# ESP_LoRa_V1_0.net
KiCad netlist of a schematic drawn in EAGLE
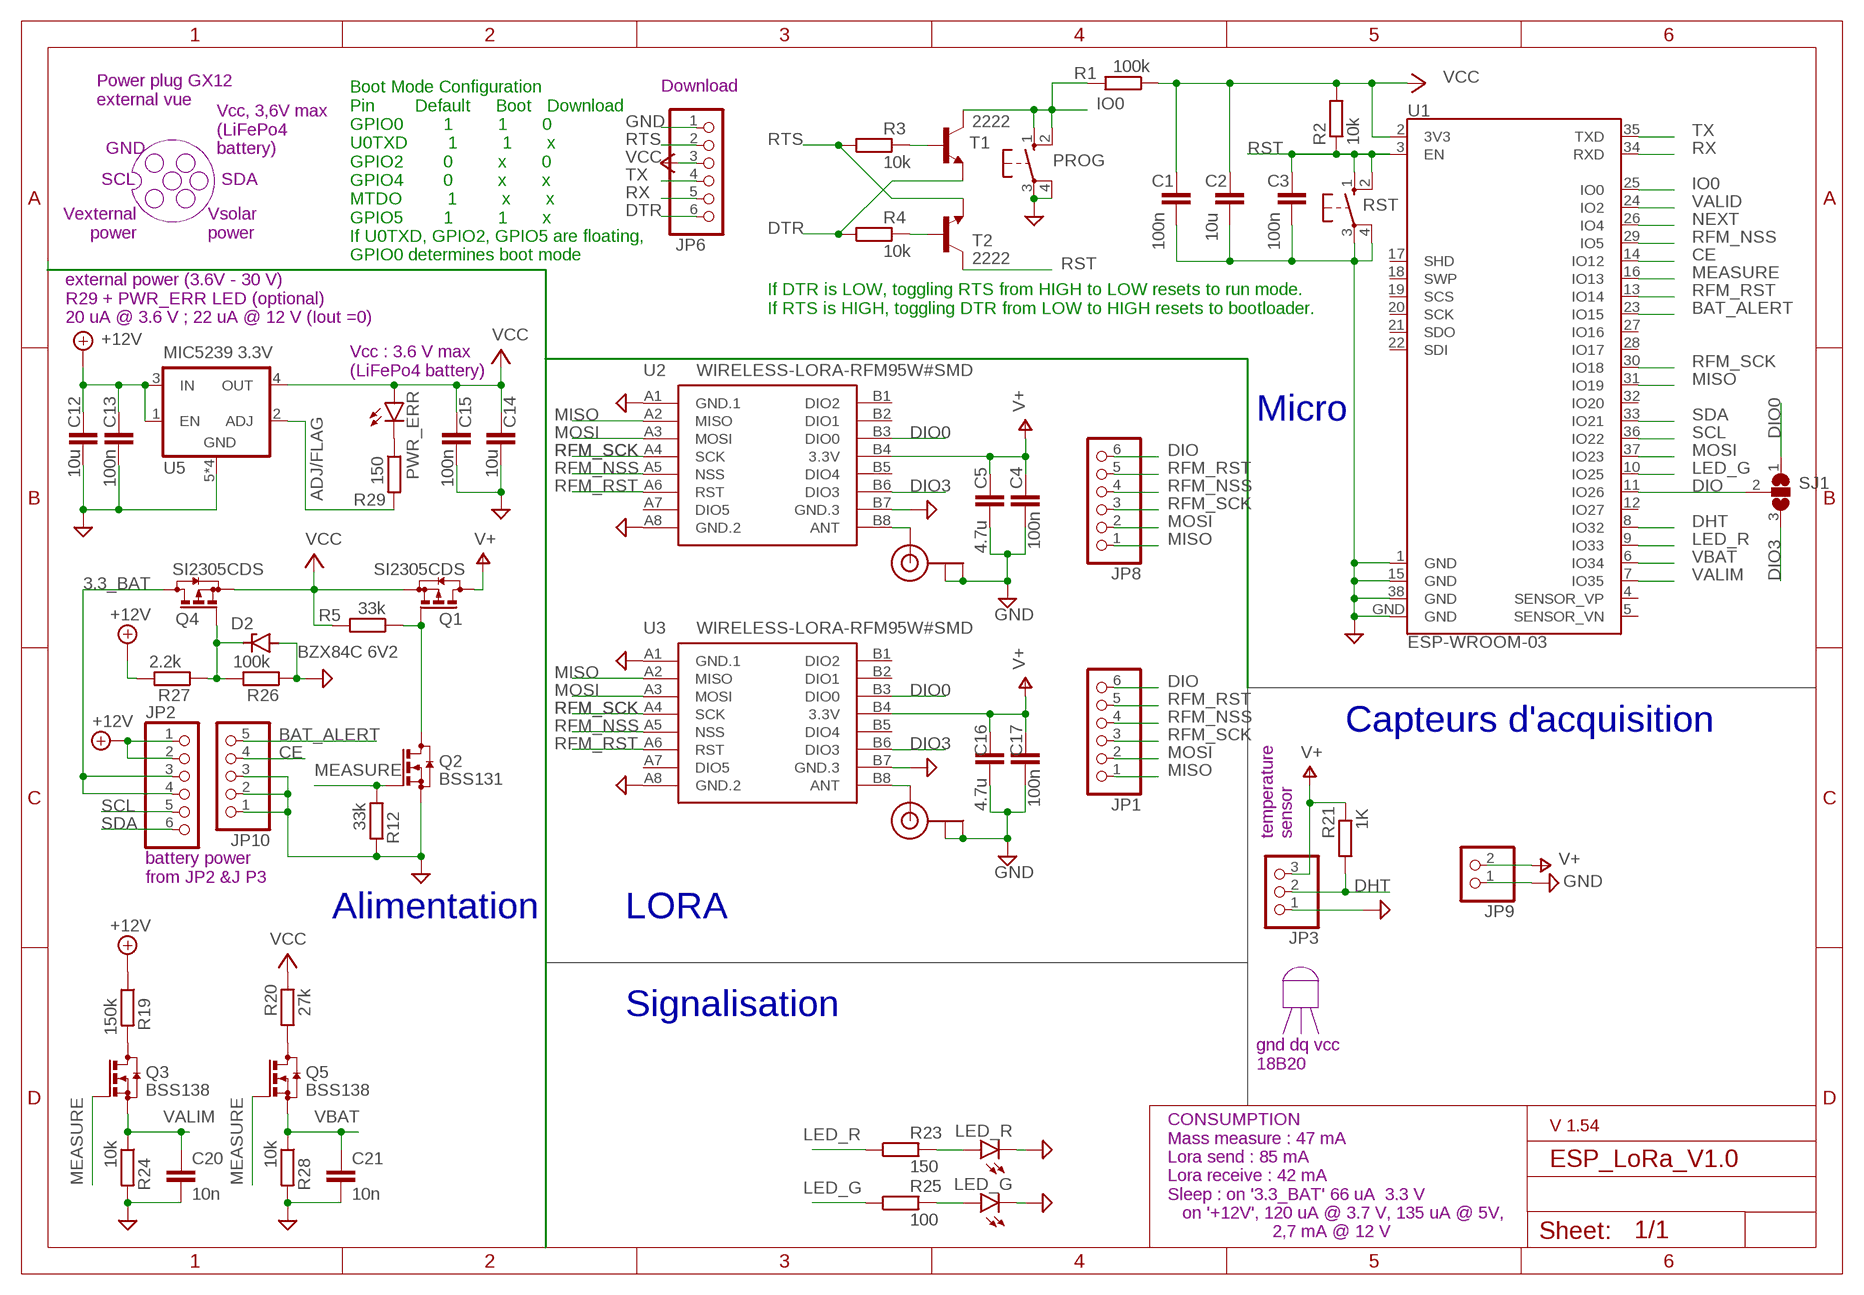
[diagram p0: schematic, sheet 1]

(export (version "E")
  (design (tool "Eeschema 10.0.6"))
  (components
    (comp (ref "C1")
      (value "100n")
      (footprint "eagle-import:C1206")
      (libsource (lib "eagle-import") (part "CC1206"))
    )
    (comp (ref "C2")
      (value "10u")
      (footprint "eagle-import:C1210")
      (libsource (lib "eagle-import") (part "CC1210"))
    )
    (comp (ref "C3")
      (value "100n")
      (footprint "eagle-import:C1206")
      (libsource (lib "eagle-import") (part "CC1206"))
    )
    (comp (ref "C4")
      (value "100n")
      (footprint "eagle-import:C1206")
      (libsource (lib "eagle-import") (part "CC1206"))
    )
    (comp (ref "C5")
      (value "4.7u")
      (footprint "eagle-import:C1210")
      (libsource (lib "eagle-import") (part "CC1210"))
    )
    (comp (ref "C12")
      (value "10u")
      (footprint "eagle-import:C1210")
      (libsource (lib "eagle-import") (part "CC1210"))
    )
    (comp (ref "C13")
      (value "100n")
      (footprint "eagle-import:C1206")
      (libsource (lib "eagle-import") (part "CC1206"))
    )
    (comp (ref "C14")
      (value "10u")
      (footprint "eagle-import:C1210")
      (libsource (lib "eagle-import") (part "CC1210"))
    )
    (comp (ref "C15")
      (value "100n")
      (footprint "eagle-import:C1206")
      (libsource (lib "eagle-import") (part "CC1206"))
    )
    (comp (ref "C16")
      (value "4.7u")
      (footprint "eagle-import:C1210")
      (libsource (lib "eagle-import") (part "CC1210"))
    )
    (comp (ref "C17")
      (value "100n")
      (footprint "eagle-import:C1206")
      (libsource (lib "eagle-import") (part "CC1206"))
    )
    (comp (ref "C20")
      (value "10n")
      (footprint "eagle-import:C1206")
      (libsource (lib "eagle-import") (part "CC1206"))
    )
    (comp (ref "C21")
      (value "10n")
      (footprint "eagle-import:C1206")
      (libsource (lib "eagle-import") (part "CC1206"))
    )
    (comp (ref "D2")
      (value "BZX84C 6V2")
      (footprint "eagle-import:TO236")
      (libsource (lib "eagle-import") (part "BZX84CSMD"))
    )
    (comp (ref "J1")
      (value "U.FL")
      (footprint "eagle-import:U.FL")
      (libsource (lib "eagle-import") (part "U.FL"))
    )
    (comp (ref "J2")
      (value "U.FL")
      (footprint "eagle-import:U.FL")
      (libsource (lib "eagle-import") (part "U.FL"))
    )
    (comp (ref "JP1")
      (value "PINHD-1X6")
      (footprint "eagle-import:1X06")
      (libsource (lib "eagle-import") (part "PINHD-1X6"))
    )
    (comp (ref "JP2")
      (value "PINHD-1X6")
      (footprint "eagle-import:1X06")
      (libsource (lib "eagle-import") (part "PINHD-1X6"))
    )
    (comp (ref "JP3")
      (value "PINHD-1X3")
      (footprint "eagle-import:1X03")
      (libsource (lib "eagle-import") (part "PINHD-1X3"))
    )
    (comp (ref "JP6")
      (value "PINHD-1X6")
      (footprint "eagle-import:1X06")
      (libsource (lib "eagle-import") (part "PINHD-1X6"))
    )
    (comp (ref "JP8")
      (value "PINHD-1X6")
      (footprint "eagle-import:1X06")
      (libsource (lib "eagle-import") (part "PINHD-1X6"))
    )
    (comp (ref "JP9")
      (value "PINHD-1X2")
      (footprint "eagle-import:1X02")
      (libsource (lib "eagle-import") (part "PINHD-1X2"))
    )
    (comp (ref "JP10")
      (value "PINHD-1X5")
      (footprint "eagle-import:1X05")
      (libsource (lib "eagle-import") (part "PINHD-1X5"))
    )
    (comp (ref "LED_G")
      (value "LEDSMT1206")
      (footprint "eagle-import:1206")
      (libsource (lib "eagle-import") (part "LEDSMT1206"))
    )
    (comp (ref "LED_R")
      (value "LEDSMT1206")
      (footprint "eagle-import:1206")
      (libsource (lib "eagle-import") (part "LEDSMT1206"))
    )
    (comp (ref "PROG")
      (value "10-XX")
      (footprint "eagle-import:B3F-10XX")
      (fields (field (name "MPN") "B3F-1000"))
      (libsource (lib "eagle-import") (part "10-XX"))
    )
    (comp (ref "PWR_ERR")
      (value "LEDSMT1206")
      (footprint "eagle-import:1206")
      (libsource (lib "eagle-import") (part "LEDSMT1206"))
    )
    (comp (ref "Q1")
      (value "SI2305CDS")
      (footprint "eagle-import:SOT23")
      (libsource (lib "eagle-import") (part "SI2305CDS"))
    )
    (comp (ref "Q2")
      (value "BSS131")
      (footprint "eagle-import:SOT23")
      (libsource (lib "eagle-import") (part "BSS131"))
    )
    (comp (ref "Q3")
      (value "BSS138")
      (footprint "eagle-import:SOT23")
      (libsource (lib "eagle-import") (part "BSS138"))
    )
    (comp (ref "Q4")
      (value "SI2305CDS")
      (footprint "eagle-import:SOT23")
      (libsource (lib "eagle-import") (part "SI2305CDS"))
    )
    (comp (ref "Q5")
      (value "BSS138")
      (footprint "eagle-import:SOT23")
      (libsource (lib "eagle-import") (part "BSS138"))
    )
    (comp (ref "R1")
      (value "100k")
      (footprint "eagle-import:R1206")
      (libsource (lib "eagle-import") (part "RR1206"))
    )
    (comp (ref "R2")
      (value "10k")
      (footprint "eagle-import:R1206")
      (libsource (lib "eagle-import") (part "RR1206"))
    )
    (comp (ref "R3")
      (value "10k")
      (footprint "eagle-import:R1206")
      (libsource (lib "eagle-import") (part "RR1206"))
    )
    (comp (ref "R4")
      (value "10k")
      (footprint "eagle-import:R1206")
      (libsource (lib "eagle-import") (part "RR1206"))
    )
    (comp (ref "R5")
      (value "33k")
      (footprint "eagle-import:R1206")
      (libsource (lib "eagle-import") (part "RR1206"))
    )
    (comp (ref "R12")
      (value "33k")
      (footprint "eagle-import:R1206")
      (libsource (lib "eagle-import") (part "RR1206"))
    )
    (comp (ref "R19")
      (value "150k")
      (footprint "eagle-import:R1206")
      (libsource (lib "eagle-import") (part "RR1206"))
    )
    (comp (ref "R20")
      (value "27k")
      (footprint "eagle-import:R1206")
      (libsource (lib "eagle-import") (part "RR1206"))
    )
    (comp (ref "R21")
      (value "1K")
      (footprint "eagle-import:R1206")
      (libsource (lib "eagle-import") (part "RR1206"))
    )
    (comp (ref "R23")
      (value "150")
      (footprint "eagle-import:R1206")
      (libsource (lib "eagle-import") (part "RR1206"))
    )
    (comp (ref "R24")
      (value "10k")
      (footprint "eagle-import:R1206")
      (libsource (lib "eagle-import") (part "RR1206"))
    )
    (comp (ref "R25")
      (value "100")
      (footprint "eagle-import:R1206")
      (libsource (lib "eagle-import") (part "RR1206"))
    )
    (comp (ref "R26")
      (value "100k")
      (footprint "eagle-import:R1206")
      (libsource (lib "eagle-import") (part "RR1206"))
    )
    (comp (ref "R27")
      (value "2.2k")
      (footprint "eagle-import:R1206")
      (libsource (lib "eagle-import") (part "RR1206"))
    )
    (comp (ref "R28")
      (value "10k")
      (footprint "eagle-import:R1206")
      (libsource (lib "eagle-import") (part "RR1206"))
    )
    (comp (ref "R29")
      (value "150")
      (footprint "eagle-import:R1206")
      (libsource (lib "eagle-import") (part "RR1206"))
    )
    (comp (ref "RST")
      (value "10-XX")
      (footprint "eagle-import:B3F-10XX")
      (fields (field (name "MPN") "B3F-1000"))
      (libsource (lib "eagle-import") (part "10-XX"))
    )
    (comp (ref "SJ1")
      (value "SJ2W")
      (footprint "eagle-import:SJ_2")
      (libsource (lib "eagle-import") (part "SJ2W"))
    )
    (comp (ref "T1")
      (value "2222")
      (footprint "eagle-import:SOT23-BEC")
      (libsource (lib "eagle-import") (part "-NPN-SOT23-BECMMBT2222ALT1"))
    )
    (comp (ref "T2")
      (value "2222")
      (footprint "eagle-import:SOT23-BEC")
      (libsource (lib "eagle-import") (part "-NPN-SOT23-BECMMBT2222ALT1"))
    )
    (comp (ref "U1")
      (value "ESP-WROOM-03")
      (footprint "eagle-import:ESP-WROOM-03")
      (libsource (lib "eagle-import") (part "ESP-WROOM-03"))
    )
    (comp (ref "U2")
      (value "WIRELESS-LORA-RFM95W#SMD")
      (footprint "eagle-import:WIRELESS-LORA-RFM95W#SMD")
      (libsource (lib "eagle-import") (part "WIRELESS-LORA-RFM95W#SMD"))
    )
    (comp (ref "U3")
      (value "WIRELESS-LORA-RFM95W#SMD")
      (footprint "eagle-import:WIRELESS-LORA-RFM95W#SMD")
      (libsource (lib "eagle-import") (part "WIRELESS-LORA-RFM95W#SMD"))
    )
    (comp (ref "U5")
      (value "MIC5239 3.3V")
      (footprint "eagle-import:MSOP08")
      (libsource (lib "eagle-import") (part "MIC5239-ADJMM"))
    )
  )
  (nets
    (net (code "1") (name "+12V") (class "Default")
      (node (ref "C12") (pin "1") (pinfunction "1_1") (pintype "passive"))
      (node (ref "C13") (pin "1") (pinfunction "1_1") (pintype "passive"))
      (node (ref "JP2") (pin "1") (pinfunction "1_1") (pintype "passive"))
      (node (ref "JP2") (pin "2") (pinfunction "2_2") (pintype "passive"))
      (node (ref "R19") (pin "1") (pinfunction "1_1") (pintype "passive"))
      (node (ref "R27") (pin "2") (pinfunction "2_2") (pintype "passive"))
      (node (ref "U5") (pin "1") (pinfunction "EN_1") (pintype "input"))
      (node (ref "U5") (pin "3") (pinfunction "IN_3") (pintype "input"))
    )
    (net (code "2") (name "/3.3_BAT") (class "Default")
      (node (ref "JP2") (pin "3") (pinfunction "3_3") (pintype "passive"))
      (node (ref "JP2") (pin "4") (pinfunction "4_4") (pintype "passive"))
      (node (ref "Q4") (pin "3") (pinfunction "D_3") (pintype "passive"))
    )
    (net (code "3") (name "/ADJ{slash}FLAG") (class "Default")
      (node (ref "R29") (pin "2") (pinfunction "2_2") (pintype "passive"))
      (node (ref "U5") (pin "2") (pinfunction "ADJ_2") (pintype "passive"))
    )
    (net (code "4") (name "/BAT_ALERT") (class "Default")
      (node (ref "JP10") (pin "5") (pinfunction "5_5") (pintype "passive"))
      (node (ref "U1") (pin "23") (pinfunction "IO15_23") (pintype "bidirectional"))
    )
    (net (code "5") (name "/CE") (class "Default")
      (node (ref "JP10") (pin "4") (pinfunction "4_4") (pintype "passive"))
      (node (ref "U1") (pin "14") (pinfunction "IO12_14") (pintype "bidirectional"))
    )
    (net (code "6") (name "/DHT") (class "Default")
      (node (ref "JP3") (pin "2") (pinfunction "2_2") (pintype "passive"))
      (node (ref "R21") (pin "1") (pinfunction "1_1") (pintype "passive"))
      (node (ref "U1") (pin "8") (pinfunction "IO32_8") (pintype "bidirectional"))
    )
    (net (code "7") (name "/DIO") (class "Default")
      (node (ref "JP1") (pin "6") (pinfunction "6_6") (pintype "passive"))
      (node (ref "JP8") (pin "6") (pinfunction "6_6") (pintype "passive"))
      (node (ref "SJ1") (pin "2") (pinfunction "2_2") (pintype "passive"))
      (node (ref "U1") (pin "11") (pinfunction "IO26_11") (pintype "bidirectional"))
    )
    (net (code "8") (name "/DIO0") (class "Default")
      (node (ref "SJ1") (pin "1") (pinfunction "1_1") (pintype "passive"))
      (node (ref "U2") (pin "B3") (pinfunction "DIO0_B3") (pintype "bidirectional"))
      (node (ref "U3") (pin "B3") (pinfunction "DIO0_B3") (pintype "bidirectional"))
    )
    (net (code "9") (name "/DIO3") (class "Default")
      (node (ref "SJ1") (pin "3") (pinfunction "3_3") (pintype "passive"))
      (node (ref "U2") (pin "B6") (pinfunction "DIO3_B6") (pintype "bidirectional"))
      (node (ref "U3") (pin "B6") (pinfunction "DIO3_B6") (pintype "bidirectional"))
    )
    (net (code "10") (name "/DTR") (class "Default")
      (node (ref "JP6") (pin "6") (pinfunction "6_6") (pintype "passive"))
      (node (ref "R4") (pin "1") (pinfunction "1_1") (pintype "passive"))
      (node (ref "T1") (pin "E") (pinfunction "E_E") (pintype "passive"))
    )
    (net (code "11") (name "/IO0") (class "Default")
      (node (ref "PROG") (pin "1") (pinfunction "S_1") (pintype "passive"))
      (node (ref "PROG") (pin "2") (pinfunction "S1_2") (pintype "passive"))
      (node (ref "R1") (pin "2") (pinfunction "2_2") (pintype "passive"))
      (node (ref "T1") (pin "C") (pinfunction "C_C") (pintype "passive"))
      (node (ref "U1") (pin "25") (pinfunction "IO0_25") (pintype "bidirectional"))
    )
    (net (code "12") (name "/LED_G") (class "Default")
      (node (ref "R25") (pin "1") (pinfunction "1_1") (pintype "passive"))
      (node (ref "U1") (pin "10") (pinfunction "IO25_10") (pintype "bidirectional"))
    )
    (net (code "13") (name "/LED_R") (class "Default")
      (node (ref "R23") (pin "1") (pinfunction "1_1") (pintype "passive"))
      (node (ref "U1") (pin "9") (pinfunction "IO33_9") (pintype "bidirectional"))
    )
    (net (code "14") (name "/MEASURE") (class "Default")
      (node (ref "Q2") (pin "1") (pinfunction "G_1") (pintype "passive"))
      (node (ref "Q3") (pin "1") (pinfunction "G_1") (pintype "passive"))
      (node (ref "Q5") (pin "1") (pinfunction "G_1") (pintype "passive"))
      (node (ref "R12") (pin "1") (pinfunction "1_1") (pintype "passive"))
      (node (ref "U1") (pin "16") (pinfunction "IO13_16") (pintype "bidirectional"))
    )
    (net (code "15") (name "/MISO") (class "Default")
      (node (ref "JP1") (pin "1") (pinfunction "1_1") (pintype "passive"))
      (node (ref "JP8") (pin "1") (pinfunction "1_1") (pintype "passive"))
      (node (ref "U1") (pin "31") (pinfunction "IO19_31") (pintype "bidirectional"))
      (node (ref "U2") (pin "A2") (pinfunction "MISO_A2") (pintype "bidirectional"))
      (node (ref "U3") (pin "A2") (pinfunction "MISO_A2") (pintype "bidirectional"))
    )
    (net (code "16") (name "/MOSI") (class "Default")
      (node (ref "JP1") (pin "2") (pinfunction "2_2") (pintype "passive"))
      (node (ref "JP8") (pin "2") (pinfunction "2_2") (pintype "passive"))
      (node (ref "U1") (pin "37") (pinfunction "IO23_37") (pintype "bidirectional"))
      (node (ref "U2") (pin "A3") (pinfunction "MOSI_A3") (pintype "bidirectional"))
      (node (ref "U3") (pin "A3") (pinfunction "MOSI_A3") (pintype "bidirectional"))
    )
    (net (code "17") (name "/NEXT") (class "Default")
      (node (ref "U1") (pin "26") (pinfunction "IO4_26") (pintype "bidirectional"))
    )
    (net (code "18") (name "/RFM_NSS") (class "Default")
      (node (ref "JP1") (pin "4") (pinfunction "4_4") (pintype "passive"))
      (node (ref "JP8") (pin "4") (pinfunction "4_4") (pintype "passive"))
      (node (ref "U1") (pin "29") (pinfunction "IO5_29") (pintype "bidirectional"))
      (node (ref "U2") (pin "A5") (pinfunction "NSS_A5") (pintype "bidirectional"))
      (node (ref "U3") (pin "A5") (pinfunction "NSS_A5") (pintype "bidirectional"))
    )
    (net (code "19") (name "/RFM_RST") (class "Default")
      (node (ref "JP1") (pin "5") (pinfunction "5_5") (pintype "passive"))
      (node (ref "JP8") (pin "5") (pinfunction "5_5") (pintype "passive"))
      (node (ref "U1") (pin "13") (pinfunction "IO14_13") (pintype "bidirectional"))
      (node (ref "U2") (pin "A6") (pinfunction "RST_A6") (pintype "bidirectional"))
      (node (ref "U3") (pin "A6") (pinfunction "RST_A6") (pintype "bidirectional"))
    )
    (net (code "20") (name "/RFM_SCK") (class "Default")
      (node (ref "JP1") (pin "3") (pinfunction "3_3") (pintype "passive"))
      (node (ref "JP8") (pin "3") (pinfunction "3_3") (pintype "passive"))
      (node (ref "U1") (pin "30") (pinfunction "IO18_30") (pintype "bidirectional"))
      (node (ref "U2") (pin "A4") (pinfunction "SCK_A4") (pintype "bidirectional"))
      (node (ref "U3") (pin "A4") (pinfunction "SCK_A4") (pintype "bidirectional"))
    )
    (net (code "21") (name "/RST") (class "Default")
      (node (ref "C3") (pin "1") (pinfunction "1_1") (pintype "passive"))
      (node (ref "R2") (pin "1") (pinfunction "1_1") (pintype "passive"))
      (node (ref "RST") (pin "1") (pinfunction "S_1") (pintype "passive"))
      (node (ref "RST") (pin "2") (pinfunction "S1_2") (pintype "passive"))
      (node (ref "T2") (pin "C") (pinfunction "C_C") (pintype "passive"))
      (node (ref "U1") (pin "3") (pinfunction "EN_3") (pintype "bidirectional"))
    )
    (net (code "22") (name "/RTS") (class "Default")
      (node (ref "JP6") (pin "2") (pinfunction "2_2") (pintype "passive"))
      (node (ref "R3") (pin "1") (pinfunction "1_1") (pintype "passive"))
      (node (ref "T2") (pin "E") (pinfunction "E_E") (pintype "passive"))
    )
    (net (code "23") (name "/RX") (class "Default")
      (node (ref "JP6") (pin "5") (pinfunction "5_5") (pintype "passive"))
      (node (ref "U1") (pin "34") (pinfunction "RXD_34") (pintype "bidirectional"))
    )
    (net (code "24") (name "/SCL") (class "Default")
      (node (ref "JP2") (pin "5") (pinfunction "5_5") (pintype "passive"))
      (node (ref "U1") (pin "36") (pinfunction "IO22_36") (pintype "bidirectional"))
    )
    (net (code "25") (name "/SDA") (class "Default")
      (node (ref "JP2") (pin "6") (pinfunction "6_6") (pintype "passive"))
      (node (ref "U1") (pin "33") (pinfunction "IO21_33") (pintype "bidirectional"))
    )
    (net (code "26") (name "/TX") (class "Default")
      (node (ref "JP6") (pin "4") (pinfunction "4_4") (pintype "passive"))
      (node (ref "U1") (pin "35") (pinfunction "TXD_35") (pintype "bidirectional"))
    )
    (net (code "27") (name "/VALID") (class "Default")
      (node (ref "U1") (pin "24") (pinfunction "IO2_24") (pintype "bidirectional"))
    )
    (net (code "28") (name "/VALIM") (class "Default")
      (node (ref "C20") (pin "1") (pinfunction "1_1") (pintype "passive"))
      (node (ref "Q3") (pin "2") (pinfunction "S_2") (pintype "passive"))
      (node (ref "R24") (pin "1") (pinfunction "1_1") (pintype "passive"))
      (node (ref "U1") (pin "7") (pinfunction "IO35_7") (pintype "bidirectional"))
    )
    (net (code "29") (name "/VBAT") (class "Default")
      (node (ref "C21") (pin "1") (pinfunction "1_1") (pintype "passive"))
      (node (ref "Q5") (pin "2") (pinfunction "S_2") (pintype "passive"))
      (node (ref "R28") (pin "1") (pinfunction "1_1") (pintype "passive"))
      (node (ref "U1") (pin "6") (pinfunction "IO34_6") (pintype "bidirectional"))
    )
    (net (code "30") (name "GND") (class "Default")
      (node (ref "C1") (pin "2") (pinfunction "2_2") (pintype "passive"))
      (node (ref "C12") (pin "2") (pinfunction "2_2") (pintype "passive"))
      (node (ref "C13") (pin "2") (pinfunction "2_2") (pintype "passive"))
      (node (ref "C14") (pin "2") (pinfunction "2_2") (pintype "passive"))
      (node (ref "C15") (pin "2") (pinfunction "2_2") (pintype "passive"))
      (node (ref "C16") (pin "2") (pinfunction "2_2") (pintype "passive"))
      (node (ref "C17") (pin "2") (pinfunction "2_2") (pintype "passive"))
      (node (ref "C2") (pin "2") (pinfunction "2_2") (pintype "passive"))
      (node (ref "C20") (pin "2") (pinfunction "2_2") (pintype "passive"))
      (node (ref "C21") (pin "2") (pinfunction "2_2") (pintype "passive"))
      (node (ref "C3") (pin "2") (pinfunction "2_2") (pintype "passive"))
      (node (ref "C4") (pin "2") (pinfunction "2_2") (pintype "passive"))
      (node (ref "C5") (pin "2") (pinfunction "2_2") (pintype "passive"))
      (node (ref "D2") (pin "A") (pinfunction "A_A") (pintype "passive"))
      (node (ref "J1") (pin "1") (pinfunction "GND_1") (pintype "passive"))
      (node (ref "J1") (pin "2") (pinfunction "GND_2") (pintype "passive"))
      (node (ref "J2") (pin "1") (pinfunction "GND_1") (pintype "passive"))
      (node (ref "J2") (pin "2") (pinfunction "GND_2") (pintype "passive"))
      (node (ref "JP10") (pin "1") (pinfunction "1_1") (pintype "passive"))
      (node (ref "JP10") (pin "2") (pinfunction "2_2") (pintype "passive"))
      (node (ref "JP10") (pin "3") (pinfunction "3_3") (pintype "passive"))
      (node (ref "JP3") (pin "1") (pinfunction "1_1") (pintype "passive"))
      (node (ref "JP6") (pin "1") (pinfunction "1_1") (pintype "passive"))
      (node (ref "JP9") (pin "1") (pinfunction "1_1") (pintype "passive"))
      (node (ref "LED_G") (pin "C") (pinfunction "C_C") (pintype "passive"))
      (node (ref "LED_R") (pin "C") (pinfunction "C_C") (pintype "passive"))
      (node (ref "PROG") (pin "3") (pinfunction "P_3") (pintype "passive"))
      (node (ref "PROG") (pin "4") (pinfunction "P1_4") (pintype "passive"))
      (node (ref "Q2") (pin "2") (pinfunction "S_2") (pintype "passive"))
      (node (ref "R12") (pin "2") (pinfunction "2_2") (pintype "passive"))
      (node (ref "R24") (pin "2") (pinfunction "2_2") (pintype "passive"))
      (node (ref "R26") (pin "1") (pinfunction "1_1") (pintype "passive"))
      (node (ref "R28") (pin "2") (pinfunction "2_2") (pintype "passive"))
      (node (ref "RST") (pin "3") (pinfunction "P_3") (pintype "passive"))
      (node (ref "RST") (pin "4") (pinfunction "P1_4") (pintype "passive"))
      (node (ref "U1") (pin "1") (pinfunction "GND_1") (pintype "bidirectional"))
      (node (ref "U1") (pin "15") (pinfunction "GND_15") (pintype "bidirectional"))
      (node (ref "U1") (pin "38") (pinfunction "GND_38") (pintype "bidirectional"))
      (node (ref "U1") (pin "GND") (pinfunction "GND_GND") (pintype "bidirectional"))
      (node (ref "U2") (pin "A1") (pinfunction "GND.1_A1") (pintype "power_in"))
      (node (ref "U2") (pin "A8") (pinfunction "GND.2_A8") (pintype "power_in"))
      (node (ref "U2") (pin "B7") (pinfunction "GND.3_B7") (pintype "power_in"))
      (node (ref "U3") (pin "A1") (pinfunction "GND.1_A1") (pintype "power_in"))
      (node (ref "U3") (pin "A8") (pinfunction "GND.2_A8") (pintype "power_in"))
      (node (ref "U3") (pin "B7") (pinfunction "GND.3_B7") (pintype "power_in"))
      (node (ref "U5") (pin "5") (pinfunction "GND_5") (pintype "power_in"))
      (node (ref "U5") (pin "6") (pinfunction "GND_6") (pintype "power_in"))
      (node (ref "U5") (pin "7") (pinfunction "GND_7") (pintype "power_in"))
      (node (ref "U5") (pin "8") (pinfunction "GND_8") (pintype "power_in"))
    )
    (net (code "31") (name "Net-(J1-SIGNAL)") (class "Default")
      (node (ref "J1") (pin "3") (pinfunction "SIGNAL_3") (pintype "passive"))
      (node (ref "U3") (pin "B8") (pinfunction "ANT_B8") (pintype "passive"))
    )
    (net (code "32") (name "Net-(J2-SIGNAL)") (class "Default")
      (node (ref "J2") (pin "3") (pinfunction "SIGNAL_3") (pintype "passive"))
      (node (ref "U2") (pin "B8") (pinfunction "ANT_B8") (pintype "passive"))
    )
    (net (code "33") (name "Net-(LED_G-PadA)") (class "Default")
      (node (ref "LED_G") (pin "A") (pinfunction "A_A") (pintype "passive"))
      (node (ref "R25") (pin "2") (pinfunction "2_2") (pintype "passive"))
    )
    (net (code "34") (name "Net-(LED_R-PadA)") (class "Default")
      (node (ref "LED_R") (pin "A") (pinfunction "A_A") (pintype "passive"))
      (node (ref "R23") (pin "2") (pinfunction "2_2") (pintype "passive"))
    )
    (net (code "35") (name "Net-(PWR_ERR-PadC)") (class "Default")
      (node (ref "PWR_ERR") (pin "C") (pinfunction "C_C") (pintype "passive"))
      (node (ref "R29") (pin "1") (pinfunction "1_1") (pintype "passive"))
    )
    (net (code "36") (name "Net-(Q1-G)") (class "Default")
      (node (ref "Q1") (pin "1") (pinfunction "G_1") (pintype "passive"))
      (node (ref "Q2") (pin "3") (pinfunction "D_3") (pintype "passive"))
      (node (ref "R5") (pin "1") (pinfunction "1_1") (pintype "passive"))
    )
    (net (code "37") (name "Net-(Q3-D)") (class "Default")
      (node (ref "Q3") (pin "3") (pinfunction "D_3") (pintype "passive"))
      (node (ref "R19") (pin "2") (pinfunction "2_2") (pintype "passive"))
    )
    (net (code "38") (name "Net-(Q4-G)") (class "Default")
      (node (ref "D2") (pin "C") (pinfunction "C_C") (pintype "passive"))
      (node (ref "Q4") (pin "1") (pinfunction "G_1") (pintype "passive"))
      (node (ref "R26") (pin "2") (pinfunction "2_2") (pintype "passive"))
      (node (ref "R27") (pin "1") (pinfunction "1_1") (pintype "passive"))
    )
    (net (code "39") (name "Net-(Q5-D)") (class "Default")
      (node (ref "Q5") (pin "3") (pinfunction "D_3") (pintype "passive"))
      (node (ref "R20") (pin "1") (pinfunction "1_1") (pintype "passive"))
    )
    (net (code "40") (name "Net-(R3-Pad2)") (class "Default")
      (node (ref "R3") (pin "2") (pinfunction "2_2") (pintype "passive"))
      (node (ref "T1") (pin "B") (pinfunction "B_B") (pintype "passive"))
    )
    (net (code "41") (name "Net-(R4-Pad2)") (class "Default")
      (node (ref "R4") (pin "2") (pinfunction "2_2") (pintype "passive"))
      (node (ref "T2") (pin "B") (pinfunction "B_B") (pintype "passive"))
    )
    (net (code "42") (name "V+") (class "Default")
      (node (ref "C16") (pin "1") (pinfunction "1_1") (pintype "passive"))
      (node (ref "C17") (pin "1") (pinfunction "1_1") (pintype "passive"))
      (node (ref "C4") (pin "1") (pinfunction "1_1") (pintype "passive"))
      (node (ref "C5") (pin "1") (pinfunction "1_1") (pintype "passive"))
      (node (ref "JP3") (pin "3") (pinfunction "3_3") (pintype "passive"))
      (node (ref "JP9") (pin "2") (pinfunction "2_2") (pintype "passive"))
      (node (ref "Q1") (pin "3") (pinfunction "D_3") (pintype "passive"))
      (node (ref "R21") (pin "2") (pinfunction "2_2") (pintype "passive"))
      (node (ref "U2") (pin "B4") (pinfunction "3.3V_B4") (pintype "power_in"))
      (node (ref "U3") (pin "B4") (pinfunction "3.3V_B4") (pintype "power_in"))
    )
    (net (code "43") (name "VCC") (class "Default")
      (node (ref "C1") (pin "1") (pinfunction "1_1") (pintype "passive"))
      (node (ref "C14") (pin "1") (pinfunction "1_1") (pintype "passive"))
      (node (ref "C15") (pin "1") (pinfunction "1_1") (pintype "passive"))
      (node (ref "C2") (pin "1") (pinfunction "1_1") (pintype "passive"))
      (node (ref "JP6") (pin "3") (pinfunction "3_3") (pintype "passive"))
      (node (ref "PWR_ERR") (pin "A") (pinfunction "A_A") (pintype "passive"))
      (node (ref "Q1") (pin "2") (pinfunction "S_2") (pintype "passive"))
      (node (ref "Q4") (pin "2") (pinfunction "S_2") (pintype "passive"))
      (node (ref "R1") (pin "1") (pinfunction "1_1") (pintype "passive"))
      (node (ref "R2") (pin "2") (pinfunction "2_2") (pintype "passive"))
      (node (ref "R20") (pin "2") (pinfunction "2_2") (pintype "passive"))
      (node (ref "R5") (pin "2") (pinfunction "2_2") (pintype "passive"))
      (node (ref "U1") (pin "2") (pinfunction "3V3_2") (pintype "bidirectional"))
      (node (ref "U5") (pin "4") (pinfunction "OUT_4") (pintype "passive"))
    )
    (net (code "44") (name "unconnected-(U1-IO16-Pad27)") (class "Default")
      (node (ref "U1") (pin "27") (pinfunction "IO16_27") (pintype "bidirectional"))
    )
    (net (code "45") (name "unconnected-(U1-IO17-Pad28)") (class "Default")
      (node (ref "U1") (pin "28") (pinfunction "IO17_28") (pintype "bidirectional"))
    )
    (net (code "46") (name "unconnected-(U1-IO20-Pad32)") (class "Default")
      (node (ref "U1") (pin "32") (pinfunction "IO20_32") (pintype "bidirectional"))
    )
    (net (code "47") (name "unconnected-(U1-IO27-Pad12)") (class "Default")
      (node (ref "U1") (pin "12") (pinfunction "IO27_12") (pintype "bidirectional"))
    )
    (net (code "48") (name "unconnected-(U1-SCK-Pad20)") (class "Default")
      (node (ref "U1") (pin "20") (pinfunction "SCK_20") (pintype "bidirectional"))
    )
    (net (code "49") (name "unconnected-(U1-SCS-Pad19)") (class "Default")
      (node (ref "U1") (pin "19") (pinfunction "SCS_19") (pintype "bidirectional"))
    )
    (net (code "50") (name "unconnected-(U1-SDI-Pad22)") (class "Default")
      (node (ref "U1") (pin "22") (pinfunction "SDI_22") (pintype "bidirectional"))
    )
    (net (code "51") (name "unconnected-(U1-SDO-Pad21)") (class "Default")
      (node (ref "U1") (pin "21") (pinfunction "SDO_21") (pintype "bidirectional"))
    )
    (net (code "52") (name "unconnected-(U1-SENSOR_VN-Pad5)") (class "Default")
      (node (ref "U1") (pin "5") (pinfunction "SENSOR_VN_5") (pintype "bidirectional"))
    )
    (net (code "53") (name "unconnected-(U1-SENSOR_VP-Pad4)") (class "Default")
      (node (ref "U1") (pin "4") (pinfunction "SENSOR_VP_4") (pintype "bidirectional"))
    )
    (net (code "54") (name "unconnected-(U1-SHD-Pad17)") (class "Default")
      (node (ref "U1") (pin "17") (pinfunction "SHD_17") (pintype "bidirectional"))
    )
    (net (code "55") (name "unconnected-(U1-SWP-Pad18)") (class "Default")
      (node (ref "U1") (pin "18") (pinfunction "SWP_18") (pintype "bidirectional"))
    )
    (net (code "56") (name "unconnected-(U2-DIO1-PadB2)") (class "Default")
      (node (ref "U2") (pin "B2") (pinfunction "DIO1_B2") (pintype "bidirectional"))
    )
    (net (code "57") (name "unconnected-(U2-DIO2-PadB1)") (class "Default")
      (node (ref "U2") (pin "B1") (pinfunction "DIO2_B1") (pintype "bidirectional"))
    )
    (net (code "58") (name "unconnected-(U2-DIO4-PadB5)") (class "Default")
      (node (ref "U2") (pin "B5") (pinfunction "DIO4_B5") (pintype "bidirectional"))
    )
    (net (code "59") (name "unconnected-(U2-DIO5-PadA7)") (class "Default")
      (node (ref "U2") (pin "A7") (pinfunction "DIO5_A7") (pintype "bidirectional"))
    )
    (net (code "60") (name "unconnected-(U3-DIO1-PadB2)") (class "Default")
      (node (ref "U3") (pin "B2") (pinfunction "DIO1_B2") (pintype "bidirectional"))
    )
    (net (code "61") (name "unconnected-(U3-DIO2-PadB1)") (class "Default")
      (node (ref "U3") (pin "B1") (pinfunction "DIO2_B1") (pintype "bidirectional"))
    )
    (net (code "62") (name "unconnected-(U3-DIO4-PadB5)") (class "Default")
      (node (ref "U3") (pin "B5") (pinfunction "DIO4_B5") (pintype "bidirectional"))
    )
    (net (code "63") (name "unconnected-(U3-DIO5-PadA7)") (class "Default")
      (node (ref "U3") (pin "A7") (pinfunction "DIO5_A7") (pintype "bidirectional"))
    )
  )
)
